# BodyTubeRev.net
KiCad netlist of a schematic drawn in Altium Designer
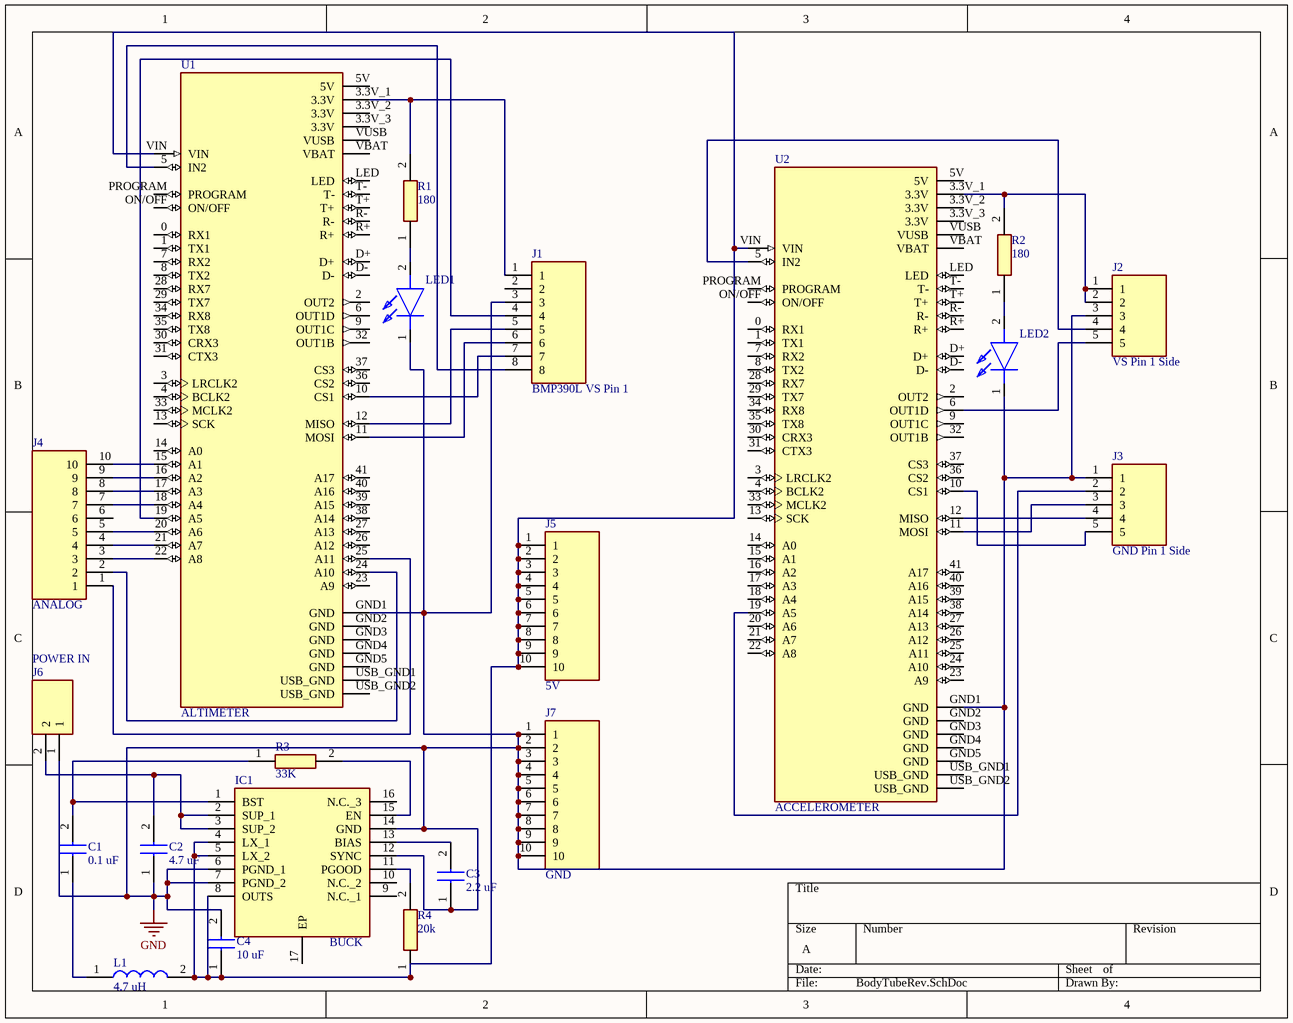
[diagram p0: BodyTubeRev.SchDoc]

(export (version "E")
  (design (tool "Eeschema 10.0.6"))
  (components
    (comp (ref "C1")
      (value "0.1 uF")
      (footprint "SamacSys:CAPC2012X88N")
      (description "Capacitor")
      (fields
        (field (name "MANUFACTURER_PART_NUMBER") "C0805C222K5RAC7025")
        (field (name "MOUSER PART NUMBER") "80-C0805C222K5RACTM")
      )
      (libsource (lib "*") (part "C0805C222K5RAC7025"))
    )
    (comp (ref "C2")
      (value "4.7 uF")
      (footprint "SamacSys:CAPC2012X140N")
      (description "Capacitor")
      (fields
        (field (name "MANUFACTURER_PART_NUMBER") "GRM21BR61H475KE51L")
        (field (name "MOUSER PART NUMBER") "81-GRM21BR61H475KE1L")
      )
      (libsource (lib "SamacSys") (part "GRM21BR61H475KE51L"))
    )
    (comp (ref "C3")
      (value "2.2 uF")
      (footprint "SamacSys:CAPC2012X140N")
      (description "Capacitor")
      (fields (field (name "MANUFACTURER_PART_NUMBER") "C0805C106K8PAC7800"))
      (libsource (lib "SamacSys") (part "C0805C106K8PAC7800"))
    )
    (comp (ref "C4")
      (value "10 uF")
      (footprint "SamacSys:CAPC2012X140N")
      (description "Capacitor")
      (fields (field (name "MANUFACTURER_PART_NUMBER") "C0805C106K8PAC7800"))
      (libsource (lib "SamacSys") (part "C0805C106K8PAC7800"))
    )
    (comp (ref "IC1")
      (value "BUCK")
      (footprint "SamacSys:SOP65P638X110-17N")
      (description "Integrated Circuit")
      (fields
        (field (name "MANUFACTURER_PART_NUMBER") "MAX16903RAUE50/V+")
        (field (name "MOUSER PART NUMBER") "700-16903RAUE50/V+")
      )
      (libsource (lib "SamacSys") (part "MAX16903RAUE50_V+"))
    )
    (comp (ref "J1")
      (value "BMP390L VS Pin 1")
      (footprint "SamacSys:HDRV8W64P0X254_1X8_2032X254X813P")
      (description "Connector")
      (fields
        (field (name "MANUFACTURER_PART_NUMBER") "DW-08-07-T-S-200")
        (field (name "MOUSER PART NUMBER") "200-DW0807TS200")
      )
      (libsource (lib "*") (part "DW-08-07-T-S-200"))
    )
    (comp (ref "J2")
      (value "VS Pin 1 Side")
      (footprint "SamacSys:HDRV5W64P0X254_1X5_1270X254X813P")
      (description "Connector")
      (fields
        (field (name "MANUFACTURER_PART_NUMBER") "DW-05-07-T-S-200")
        (field (name "MOUSER PART NUMBER") "200-DW0507TS200")
      )
      (libsource (lib "*") (part "DW-05-07-T-S-200"))
    )
    (comp (ref "J3")
      (value "GND Pin 1 Side")
      (footprint "SamacSys:HDRV5W64P0X254_1X5_1270X254X813P")
      (description "Connector")
      (fields
        (field (name "MANUFACTURER_PART_NUMBER") "DW-05-07-T-S-200")
        (field (name "MOUSER PART NUMBER") "200-DW0507TS200")
      )
      (libsource (lib "*") (part "DW-05-07-T-S-200"))
    )
    (comp (ref "J4")
      (value "ANALOG")
      (footprint "SamacSys:RHDR10W80P0X254_1X10_2590X254X850P")
      (description "Connector")
      (fields (field (name "MANUFACTURER_PART_NUMBER") "PPTC101LFBN-RC"))
      (libsource (lib "") (part "PPTC101LFBN-RC_1"))
    )
    (comp (ref "J5")
      (value "5V")
      (footprint "SamacSys:RHDR10W80P0X254_1X10_2590X254X850P")
      (description "Connector")
      (fields (field (name "MANUFACTURER_PART_NUMBER") "PPTC101LFBN-RC"))
      (libsource (lib "*") (part "PPTC101LFBN-RC"))
    )
    (comp (ref "J6")
      (value "POWER IN")
      (footprint "SamacSys:0436500201")
      (description "Connector")
      (fields (field (name "MANUFACTURER_PART_NUMBER") "0436500201"))
      (libsource (lib "SamacSys") (part "0436500201"))
    )
    (comp (ref "J7")
      (value "GND")
      (footprint "SamacSys:RHDR10W80P0X254_1X10_2590X254X850P")
      (description "Connector")
      (fields (field (name "MANUFACTURER_PART_NUMBER") "PPTC101LFBN-RC"))
      (libsource (lib "*") (part "PPTC101LFBN-RC"))
    )
    (comp (ref "L1")
      (value "4.7 uH")
      (footprint "SamacSys:LQM2HPN1R0MG0L")
      (description "Inductor")
      (fields
        (field (name "MANUFACTURER_PART_NUMBER") "LQH2HPN4R7MGRL")
        (field (name "MOUSER PART NUMBER") "81-LQH2HPN4R7MGRL")
      )
      (libsource (lib "SamacSys") (part "LQH2HPN4R7MGRL"))
    )
    (comp (ref "LED1")
      (value "~")
      (footprint "SamacSys:LEDC2012X80N")
      (description "LED")
      (fields
        (field (name "MANUFACTURER_PART_NUMBER") "HSMG-C170")
        (field (name "MOUSER PART NUMBER") "630-HSMG-C170")
      )
      (libsource (lib "SamacSys") (part "HSMG-C170"))
    )
    (comp (ref "LED2")
      (value "~")
      (footprint "SamacSys:LEDC2012X80N")
      (description "LED")
      (fields
        (field (name "MANUFACTURER_PART_NUMBER") "HSMG-C170")
        (field (name "MOUSER PART NUMBER") "630-HSMG-C170")
      )
      (libsource (lib "SamacSys") (part "HSMG-C170"))
    )
    (comp (ref "R1")
      (value "180")
      (footprint "SamacSys:ERJ6EN_(0805)")
      (description "Resistor")
      (fields
        (field (name "MANUFACTURER_PART_NUMBER") "ERJ-6ENF1800V")
        (field (name "MOUSER PART NUMBER") "667-ERJ-6ENF1800V")
      )
      (libsource (lib "SamacSys") (part "ERJ-6ENF1800V"))
    )
    (comp (ref "R2")
      (value "180")
      (footprint "SamacSys:ERJ6EN_(0805)")
      (description "Resistor")
      (fields
        (field (name "MANUFACTURER_PART_NUMBER") "ERJ-6ENF1800V")
        (field (name "MOUSER PART NUMBER") "667-ERJ-6ENF1800V")
      )
      (libsource (lib "SamacSys") (part "ERJ-6ENF1800V"))
    )
    (comp (ref "R3")
      (value "33K")
      (footprint "SamacSys:ERJ6ENF1000V")
      (description "Resistor")
      (fields
        (field (name "MANUFACTURER_PART_NUMBER") "ERJ-6ENF33R0V")
        (field (name "MOUSER PART NUMBER") "667-ERJ-6ENF33R0V")
      )
      (libsource (lib "*") (part "ERJ-6ENF33R0V"))
    )
    (comp (ref "R4")
      (value "20k")
      (footprint "SamacSys:RESC2012X70N")
      (description "Resistor")
      (fields
        (field (name "MANUFACTURER_PART_NUMBER") "ERJ-6GEYJ203V")
        (field (name "MOUSER PART NUMBER") "667-ERJ-6GEYJ203V")
      )
      (libsource (lib "SamacSys") (part "ERJ-6GEYJ203V"))
    )
    (comp (ref "U1")
      (value "ALTIMETER")
      (footprint "MODULE_DEV-16771")
      (description "RT1062 Teensy 4.1 i.MX ARM Cortex-M7 MPU Embedded Evaluation Board")
      (fields (field (name "MP") "DEV-16771"))
      (libsource (lib "DEV-16771") (part "DEV-16771"))
    )
    (comp (ref "U2")
      (value "ACCELEROMETER")
      (footprint "MODULE_DEV-16771")
      (description "RT1062 Teensy 4.1 i.MX ARM Cortex-M7 MPU Embedded Evaluation Board")
      (fields (field (name "MP") "DEV-16771"))
      (libsource (lib "DEV-16771") (part "DEV-16771"))
    )
  )
  (nets
    (net (code "1") (name "GND") (class "Default")
      (node (ref "C2") (pin "1") (pinfunction "1_1") (pintype "passive"))
      (node (ref "C3") (pin "1") (pinfunction "1_1") (pintype "passive"))
      (node (ref "C4") (pin "2") (pinfunction "2_2") (pintype "passive"))
      (node (ref "IC1") (pin "12") (pinfunction "SYNC_12") (pintype "passive"))
      (node (ref "IC1") (pin "14") (pinfunction "GND_14") (pintype "passive"))
      (node (ref "IC1") (pin "6") (pinfunction "PGND_1_6") (pintype "passive"))
      (node (ref "IC1") (pin "7") (pinfunction "PGND_2_7") (pintype "passive"))
      (node (ref "J1") (pin "3") (pinfunction "3_3") (pintype "passive"))
      (node (ref "J2") (pin "3") (pinfunction "3_3") (pintype "passive"))
      (node (ref "J3") (pin "1") (pinfunction "1_1") (pintype "passive"))
      (node (ref "J6") (pin "1") (pinfunction "1_1") (pintype "passive"))
      (node (ref "J7") (pin "1") (pinfunction "1_1") (pintype "passive"))
      (node (ref "J7") (pin "10") (pinfunction "10_10") (pintype "passive"))
      (node (ref "J7") (pin "2") (pinfunction "2_2") (pintype "passive"))
      (node (ref "J7") (pin "3") (pinfunction "3_3") (pintype "passive"))
      (node (ref "J7") (pin "4") (pinfunction "4_4") (pintype "passive"))
      (node (ref "J7") (pin "5") (pinfunction "5_5") (pintype "passive"))
      (node (ref "J7") (pin "6") (pinfunction "6_6") (pintype "passive"))
      (node (ref "J7") (pin "7") (pinfunction "7_7") (pintype "passive"))
      (node (ref "J7") (pin "8") (pinfunction "8_8") (pintype "passive"))
      (node (ref "J7") (pin "9") (pinfunction "9_9") (pintype "passive"))
      (node (ref "LED1") (pin "1") (pinfunction "K_1") (pintype "passive"))
      (node (ref "LED2") (pin "1") (pinfunction "K_1") (pintype "passive"))
      (node (ref "U1") (pin "GND1") (pinfunction "GND_GND1") (pintype "power_in"))
      (node (ref "U2") (pin "GND1") (pinfunction "GND_GND1") (pintype "power_in"))
    )
    (net (code "2") (name "Net-(C1-Pad1)") (class "Default")
      (node (ref "C1") (pin "1") (pinfunction "1_1") (pintype "passive"))
      (node (ref "L1") (pin "1") (pinfunction "1_1") (pintype "passive"))
    )
    (net (code "3") (name "Net-(IC1-BIAS)") (class "Default")
      (node (ref "C3") (pin "2") (pinfunction "2_2") (pintype "passive"))
      (node (ref "IC1") (pin "13") (pinfunction "BIAS_13") (pintype "passive"))
    )
    (net (code "4") (name "Net-(IC1-BST)") (class "Default")
      (node (ref "C1") (pin "2") (pinfunction "2_2") (pintype "passive"))
      (node (ref "IC1") (pin "1") (pinfunction "BST_1") (pintype "passive"))
      (node (ref "R3") (pin "1") (pinfunction "1_1") (pintype "passive"))
    )
    (net (code "5") (name "Net-(IC1-EN)") (class "Default")
      (node (ref "IC1") (pin "15") (pinfunction "EN_15") (pintype "passive"))
      (node (ref "R3") (pin "2") (pinfunction "2_2") (pintype "passive"))
    )
    (net (code "6") (name "Net-(IC1-LX_1)") (class "Default")
      (node (ref "C4") (pin "1") (pinfunction "1_1") (pintype "passive"))
      (node (ref "IC1") (pin "4") (pinfunction "LX_1_4") (pintype "passive"))
      (node (ref "IC1") (pin "5") (pinfunction "LX_2_5") (pintype "passive"))
      (node (ref "IC1") (pin "8") (pinfunction "OUTS_8") (pintype "passive"))
      (node (ref "J5") (pin "1") (pinfunction "1_1") (pintype "passive"))
      (node (ref "J5") (pin "10") (pinfunction "10_10") (pintype "passive"))
      (node (ref "J5") (pin "2") (pinfunction "2_2") (pintype "passive"))
      (node (ref "J5") (pin "3") (pinfunction "3_3") (pintype "passive"))
      (node (ref "J5") (pin "4") (pinfunction "4_4") (pintype "passive"))
      (node (ref "J5") (pin "5") (pinfunction "5_5") (pintype "passive"))
      (node (ref "J5") (pin "6") (pinfunction "6_6") (pintype "passive"))
      (node (ref "J5") (pin "7") (pinfunction "7_7") (pintype "passive"))
      (node (ref "J5") (pin "8") (pinfunction "8_8") (pintype "passive"))
      (node (ref "J5") (pin "9") (pinfunction "9_9") (pintype "passive"))
      (node (ref "L1") (pin "2") (pinfunction "2_2") (pintype "passive"))
      (node (ref "R4") (pin "1") (pinfunction "1_1") (pintype "passive"))
      (node (ref "U1") (pin "VIN") (pinfunction "VIN_VIN") (pintype "input"))
      (node (ref "U2") (pin "VIN") (pinfunction "VIN_VIN") (pintype "input"))
    )
    (net (code "7") (name "Net-(IC1-PGOOD)") (class "Default")
      (node (ref "IC1") (pin "11") (pinfunction "PGOOD_11") (pintype "passive"))
      (node (ref "R4") (pin "2") (pinfunction "2_2") (pintype "passive"))
    )
    (net (code "8") (name "Net-(IC1-SUP_1)") (class "Default")
      (node (ref "C2") (pin "2") (pinfunction "2_2") (pintype "passive"))
      (node (ref "IC1") (pin "2") (pinfunction "SUP_1_2") (pintype "passive"))
      (node (ref "IC1") (pin "3") (pinfunction "SUP_2_3") (pintype "passive"))
      (node (ref "J6") (pin "2") (pinfunction "2_2") (pintype "passive"))
    )
    (net (code "9") (name "Net-(J1-Pad1)") (class "Default")
      (node (ref "J1") (pin "1") (pinfunction "1_1") (pintype "passive"))
      (node (ref "R1") (pin "2") (pinfunction "2_2") (pintype "passive"))
      (node (ref "U1") (pin "3.3V_1") (pinfunction "3.3V_3.3V_1") (pintype "power_in"))
    )
    (net (code "10") (name "Net-(J2-Pad1)") (class "Default")
      (node (ref "J2") (pin "1") (pinfunction "1_1") (pintype "passive"))
      (node (ref "J2") (pin "2") (pinfunction "2_2") (pintype "passive"))
      (node (ref "R2") (pin "2") (pinfunction "2_2") (pintype "passive"))
      (node (ref "U2") (pin "3.3V_1") (pinfunction "3.3V_3.3V_1") (pintype "power_in"))
    )
    (net (code "11") (name "Net-(LED1-A)") (class "Default")
      (node (ref "LED1") (pin "2") (pinfunction "A_2") (pintype "passive"))
      (node (ref "R1") (pin "1") (pinfunction "1_1") (pintype "passive"))
    )
    (net (code "12") (name "Net-(LED2-A)") (class "Default")
      (node (ref "LED2") (pin "2") (pinfunction "A_2") (pintype "passive"))
      (node (ref "R2") (pin "1") (pinfunction "1_1") (pintype "passive"))
    )
    (net (code "13") (name "Net-(U1-A1)") (class "Default")
      (node (ref "J4") (pin "10") (pinfunction "10_10") (pintype "passive"))
      (node (ref "U1") (pin "15") (pinfunction "A1_15") (pintype "bidirectional"))
    )
    (net (code "14") (name "Net-(U1-A2)") (class "Default")
      (node (ref "J4") (pin "9") (pinfunction "9_9") (pintype "passive"))
      (node (ref "U1") (pin "16") (pinfunction "A2_16") (pintype "bidirectional"))
    )
    (net (code "15") (name "Net-(U1-A3)") (class "Default")
      (node (ref "J4") (pin "8") (pinfunction "8_8") (pintype "passive"))
      (node (ref "U1") (pin "17") (pinfunction "A3_17") (pintype "bidirectional"))
    )
    (net (code "16") (name "Net-(U1-A4)") (class "Default")
      (node (ref "J4") (pin "7") (pinfunction "7_7") (pintype "passive"))
      (node (ref "U1") (pin "18") (pinfunction "A4_18") (pintype "bidirectional"))
    )
    (net (code "17") (name "Net-(U1-A5)") (class "Default")
      (node (ref "J1") (pin "4") (pinfunction "4_4") (pintype "passive"))
      (node (ref "U1") (pin "19") (pinfunction "A5_19") (pintype "bidirectional"))
    )
    (net (code "18") (name "Net-(U1-A6)") (class "Default")
      (node (ref "J4") (pin "5") (pinfunction "5_5") (pintype "passive"))
      (node (ref "U1") (pin "20") (pinfunction "A6_20") (pintype "bidirectional"))
    )
    (net (code "19") (name "Net-(U1-A7)") (class "Default")
      (node (ref "J4") (pin "4") (pinfunction "4_4") (pintype "passive"))
      (node (ref "U1") (pin "21") (pinfunction "A7_21") (pintype "bidirectional"))
    )
    (net (code "20") (name "Net-(U1-A8)") (class "Default")
      (node (ref "J4") (pin "3") (pinfunction "3_3") (pintype "passive"))
      (node (ref "U1") (pin "22") (pinfunction "A8_22") (pintype "bidirectional"))
    )
    (net (code "21") (name "Net-(U1-A10)") (class "Default")
      (node (ref "J4") (pin "2") (pinfunction "2_2") (pintype "passive"))
      (node (ref "U1") (pin "24") (pinfunction "A10_24") (pintype "bidirectional"))
    )
    (net (code "22") (name "Net-(U1-A11)") (class "Default")
      (node (ref "J4") (pin "1") (pinfunction "1_1") (pintype "passive"))
      (node (ref "U1") (pin "25") (pinfunction "A11_25") (pintype "bidirectional"))
    )
    (net (code "23") (name "Net-(U1-CS1)") (class "Default")
      (node (ref "J1") (pin "7") (pinfunction "7_7") (pintype "passive"))
      (node (ref "U1") (pin "10") (pinfunction "CS1_10") (pintype "bidirectional"))
    )
    (net (code "24") (name "Net-(U1-IN2)") (class "Default")
      (node (ref "J1") (pin "8") (pinfunction "8_8") (pintype "passive"))
      (node (ref "U1") (pin "5") (pinfunction "IN2_5") (pintype "bidirectional"))
    )
    (net (code "25") (name "Net-(U1-MISO)") (class "Default")
      (node (ref "J1") (pin "5") (pinfunction "5_5") (pintype "passive"))
      (node (ref "U1") (pin "12") (pinfunction "MISO_12") (pintype "bidirectional"))
    )
    (net (code "26") (name "Net-(U1-MOSI)") (class "Default")
      (node (ref "J1") (pin "6") (pinfunction "6_6") (pintype "passive"))
      (node (ref "U1") (pin "11") (pinfunction "MOSI_11") (pintype "bidirectional"))
    )
    (net (code "27") (name "Net-(U2-A5)") (class "Default")
      (node (ref "J3") (pin "2") (pinfunction "2_2") (pintype "passive"))
      (node (ref "U2") (pin "19") (pinfunction "A5_19") (pintype "bidirectional"))
    )
    (net (code "28") (name "Net-(U2-CS1)") (class "Default")
      (node (ref "J3") (pin "5") (pinfunction "5_5") (pintype "passive"))
      (node (ref "U2") (pin "10") (pinfunction "CS1_10") (pintype "bidirectional"))
    )
    (net (code "29") (name "Net-(U2-IN2)") (class "Default")
      (node (ref "J2") (pin "4") (pinfunction "4_4") (pintype "passive"))
      (node (ref "U2") (pin "5") (pinfunction "IN2_5") (pintype "bidirectional"))
    )
    (net (code "30") (name "Net-(U2-MISO)") (class "Default")
      (node (ref "J3") (pin "4") (pinfunction "4_4") (pintype "passive"))
      (node (ref "U2") (pin "12") (pinfunction "MISO_12") (pintype "bidirectional"))
    )
    (net (code "31") (name "Net-(U2-MOSI)") (class "Default")
      (node (ref "J3") (pin "3") (pinfunction "3_3") (pintype "passive"))
      (node (ref "U2") (pin "11") (pinfunction "MOSI_11") (pintype "bidirectional"))
    )
    (net (code "32") (name "Net-(U2-OUT1D)") (class "Default")
      (node (ref "J2") (pin "5") (pinfunction "5_5") (pintype "passive"))
      (node (ref "U2") (pin "6") (pinfunction "OUT1D_6") (pintype "output"))
    )
    (net (code "33") (name "unconnected-(IC1-EP-Pad17)") (class "Default")
      (node (ref "IC1") (pin "17") (pinfunction "EP_17") (pintype "passive"))
    )
    (net (code "34") (name "unconnected-(IC1-N.C._1-Pad9)") (class "Default")
      (node (ref "IC1") (pin "9") (pinfunction "N.C._1_9") (pintype "passive"))
    )
    (net (code "35") (name "unconnected-(IC1-N.C._2-Pad10)") (class "Default")
      (node (ref "IC1") (pin "10") (pinfunction "N.C._2_10") (pintype "passive"))
    )
    (net (code "36") (name "unconnected-(IC1-N.C._3-Pad16)") (class "Default")
      (node (ref "IC1") (pin "16") (pinfunction "N.C._3_16") (pintype "passive"))
    )
    (net (code "37") (name "unconnected-(J1-Pad2)") (class "Default")
      (node (ref "J1") (pin "2") (pinfunction "2_2") (pintype "passive"))
    )
    (net (code "38") (name "unconnected-(J4-Pad6)") (class "Default")
      (node (ref "J4") (pin "6") (pinfunction "6_6") (pintype "passive"))
    )
    (net (code "39") (name "unconnected-(U1-3.3V-Pad3.3V_2)") (class "Default")
      (node (ref "U1") (pin "3.3V_2") (pinfunction "3.3V_3.3V_2") (pintype "power_in"))
    )
    (net (code "40") (name "unconnected-(U1-3.3V-Pad3.3V_3)") (class "Default")
      (node (ref "U1") (pin "3.3V_3") (pinfunction "3.3V_3.3V_3") (pintype "power_in"))
    )
    (net (code "41") (name "unconnected-(U1-A0-Pad14)") (class "Default")
      (node (ref "U1") (pin "14") (pinfunction "A0_14") (pintype "bidirectional"))
    )
    (net (code "42") (name "unconnected-(U1-A9-Pad23)") (class "Default")
      (node (ref "U1") (pin "23") (pinfunction "A9_23") (pintype "bidirectional"))
    )
    (net (code "43") (name "unconnected-(U1-A12-Pad26)") (class "Default")
      (node (ref "U1") (pin "26") (pinfunction "A12_26") (pintype "bidirectional"))
    )
    (net (code "44") (name "unconnected-(U1-A13-Pad27)") (class "Default")
      (node (ref "U1") (pin "27") (pinfunction "A13_27") (pintype "bidirectional"))
    )
    (net (code "45") (name "unconnected-(U1-A14-Pad38)") (class "Default")
      (node (ref "U1") (pin "38") (pinfunction "A14_38") (pintype "bidirectional"))
    )
    (net (code "46") (name "unconnected-(U1-A15-Pad39)") (class "Default")
      (node (ref "U1") (pin "39") (pinfunction "A15_39") (pintype "bidirectional"))
    )
    (net (code "47") (name "unconnected-(U1-A16-Pad40)") (class "Default")
      (node (ref "U1") (pin "40") (pinfunction "A16_40") (pintype "bidirectional"))
    )
    (net (code "48") (name "unconnected-(U1-A17-Pad41)") (class "Default")
      (node (ref "U1") (pin "41") (pinfunction "A17_41") (pintype "bidirectional"))
    )
    (net (code "49") (name "unconnected-(U1-BCLK2-Pad4)") (class "Default")
      (node (ref "U1") (pin "4") (pinfunction "BCLK2_4") (pintype "bidirectional"))
    )
    (net (code "50") (name "unconnected-(U1-CRX3-Pad30)") (class "Default")
      (node (ref "U1") (pin "30") (pinfunction "CRX3_30") (pintype "bidirectional"))
    )
    (net (code "51") (name "unconnected-(U1-CS2-Pad36)") (class "Default")
      (node (ref "U1") (pin "36") (pinfunction "CS2_36") (pintype "bidirectional"))
    )
    (net (code "52") (name "unconnected-(U1-CS3-Pad37)") (class "Default")
      (node (ref "U1") (pin "37") (pinfunction "CS3_37") (pintype "bidirectional"))
    )
    (net (code "53") (name "unconnected-(U1-CTX3-Pad31)") (class "Default")
      (node (ref "U1") (pin "31") (pinfunction "CTX3_31") (pintype "bidirectional"))
    )
    (net (code "54") (name "unconnected-(U1-GND-PadGND2)") (class "Default")
      (node (ref "U1") (pin "GND2") (pinfunction "GND_GND2") (pintype "power_in"))
    )
    (net (code "55") (name "unconnected-(U1-GND-PadGND3)") (class "Default")
      (node (ref "U1") (pin "GND3") (pinfunction "GND_GND3") (pintype "power_in"))
    )
    (net (code "56") (name "unconnected-(U1-GND-PadGND4)") (class "Default")
      (node (ref "U1") (pin "GND4") (pinfunction "GND_GND4") (pintype "power_in"))
    )
    (net (code "57") (name "unconnected-(U1-GND-PadGND5)") (class "Default")
      (node (ref "U1") (pin "GND5") (pinfunction "GND_GND5") (pintype "power_in"))
    )
    (net (code "58") (name "unconnected-(U1-LRCLK2-Pad3)") (class "Default")
      (node (ref "U1") (pin "3") (pinfunction "LRCLK2_3") (pintype "bidirectional"))
    )
    (net (code "59") (name "unconnected-(U1-MCLK2-Pad33)") (class "Default")
      (node (ref "U1") (pin "33") (pinfunction "MCLK2_33") (pintype "bidirectional"))
    )
    (net (code "60") (name "unconnected-(U1-OUT1B-Pad32)") (class "Default")
      (node (ref "U1") (pin "32") (pinfunction "OUT1B_32") (pintype "output"))
    )
    (net (code "61") (name "unconnected-(U1-OUT1C-Pad9)") (class "Default")
      (node (ref "U1") (pin "9") (pinfunction "OUT1C_9") (pintype "output"))
    )
    (net (code "62") (name "unconnected-(U1-OUT1D-Pad6)") (class "Default")
      (node (ref "U1") (pin "6") (pinfunction "OUT1D_6") (pintype "output"))
    )
    (net (code "63") (name "unconnected-(U1-OUT2-Pad2)") (class "Default")
      (node (ref "U1") (pin "2") (pinfunction "OUT2_2") (pintype "output"))
    )
    (net (code "64") (name "unconnected-(U1-Pad5V)") (class "Default")
      (node (ref "U1") (pin "5V") (pinfunction "5V_5V") (pintype "power_in"))
    )
    (net (code "65") (name "unconnected-(U1-PadD+)") (class "Default")
      (node (ref "U1") (pin "D+") (pinfunction "D+_D+") (pintype "bidirectional"))
    )
    (net (code "66") (name "unconnected-(U1-PadD-)") (class "Default")
      (node (ref "U1") (pin "D-") (pinfunction "D-_D-") (pintype "bidirectional"))
    )
    (net (code "67") (name "unconnected-(U1-PadLED)") (class "Default")
      (node (ref "U1") (pin "LED") (pinfunction "LED_LED") (pintype "bidirectional"))
    )
    (net (code "68") (name "unconnected-(U1-PadON{slash}OFF)") (class "Default")
      (node (ref "U1") (pin "ON/OFF") (pinfunction "ON/OFF_ON/OFF") (pintype "bidirectional"))
    )
    (net (code "69") (name "unconnected-(U1-PadPROGRAM)") (class "Default")
      (node (ref "U1") (pin "PROGRAM") (pinfunction "PROGRAM_PROGRAM") (pintype "bidirectional"))
    )
    (net (code "70") (name "unconnected-(U1-PadR+)") (class "Default")
      (node (ref "U1") (pin "R+") (pinfunction "R+_R+") (pintype "bidirectional"))
    )
    (net (code "71") (name "unconnected-(U1-PadR-)") (class "Default")
      (node (ref "U1") (pin "R-") (pinfunction "R-_R-") (pintype "bidirectional"))
    )
    (net (code "72") (name "unconnected-(U1-PadT+)") (class "Default")
      (node (ref "U1") (pin "T+") (pinfunction "T+_T+") (pintype "bidirectional"))
    )
    (net (code "73") (name "unconnected-(U1-PadT-)") (class "Default")
      (node (ref "U1") (pin "T-") (pinfunction "T-_T-") (pintype "bidirectional"))
    )
    (net (code "74") (name "unconnected-(U1-PadVBAT)") (class "Default")
      (node (ref "U1") (pin "VBAT") (pinfunction "VBAT_VBAT") (pintype "passive"))
    )
    (net (code "75") (name "unconnected-(U1-PadVUSB)") (class "Default")
      (node (ref "U1") (pin "VUSB") (pinfunction "VUSB_VUSB") (pintype "passive"))
    )
    (net (code "76") (name "unconnected-(U1-RX1-Pad0)") (class "Default")
      (node (ref "U1") (pin "0") (pinfunction "RX1_0") (pintype "bidirectional"))
    )
    (net (code "77") (name "unconnected-(U1-RX2-Pad7)") (class "Default")
      (node (ref "U1") (pin "7") (pinfunction "RX2_7") (pintype "bidirectional"))
    )
    (net (code "78") (name "unconnected-(U1-RX7-Pad28)") (class "Default")
      (node (ref "U1") (pin "28") (pinfunction "RX7_28") (pintype "bidirectional"))
    )
    (net (code "79") (name "unconnected-(U1-RX8-Pad34)") (class "Default")
      (node (ref "U1") (pin "34") (pinfunction "RX8_34") (pintype "bidirectional"))
    )
    (net (code "80") (name "unconnected-(U1-SCK-Pad13)") (class "Default")
      (node (ref "U1") (pin "13") (pinfunction "SCK_13") (pintype "bidirectional"))
    )
    (net (code "81") (name "unconnected-(U1-TX1-Pad1)") (class "Default")
      (node (ref "U1") (pin "1") (pinfunction "TX1_1") (pintype "bidirectional"))
    )
    (net (code "82") (name "unconnected-(U1-TX2-Pad8)") (class "Default")
      (node (ref "U1") (pin "8") (pinfunction "TX2_8") (pintype "bidirectional"))
    )
    (net (code "83") (name "unconnected-(U1-TX7-Pad29)") (class "Default")
      (node (ref "U1") (pin "29") (pinfunction "TX7_29") (pintype "bidirectional"))
    )
    (net (code "84") (name "unconnected-(U1-TX8-Pad35)") (class "Default")
      (node (ref "U1") (pin "35") (pinfunction "TX8_35") (pintype "bidirectional"))
    )
    (net (code "85") (name "unconnected-(U1-USB_GND-PadUSB_GND1)") (class "Default")
      (node (ref "U1") (pin "USB_GND1") (pinfunction "USB_GND_USB_GND1") (pintype "power_in"))
    )
    (net (code "86") (name "unconnected-(U1-USB_GND-PadUSB_GND2)") (class "Default")
      (node (ref "U1") (pin "USB_GND2") (pinfunction "USB_GND_USB_GND2") (pintype "power_in"))
    )
    (net (code "87") (name "unconnected-(U2-3.3V-Pad3.3V_2)") (class "Default")
      (node (ref "U2") (pin "3.3V_2") (pinfunction "3.3V_3.3V_2") (pintype "power_in"))
    )
    (net (code "88") (name "unconnected-(U2-3.3V-Pad3.3V_3)") (class "Default")
      (node (ref "U2") (pin "3.3V_3") (pinfunction "3.3V_3.3V_3") (pintype "power_in"))
    )
    (net (code "89") (name "unconnected-(U2-A0-Pad14)") (class "Default")
      (node (ref "U2") (pin "14") (pinfunction "A0_14") (pintype "bidirectional"))
    )
    (net (code "90") (name "unconnected-(U2-A1-Pad15)") (class "Default")
      (node (ref "U2") (pin "15") (pinfunction "A1_15") (pintype "bidirectional"))
    )
    (net (code "91") (name "unconnected-(U2-A2-Pad16)") (class "Default")
      (node (ref "U2") (pin "16") (pinfunction "A2_16") (pintype "bidirectional"))
    )
    (net (code "92") (name "unconnected-(U2-A3-Pad17)") (class "Default")
      (node (ref "U2") (pin "17") (pinfunction "A3_17") (pintype "bidirectional"))
    )
    (net (code "93") (name "unconnected-(U2-A4-Pad18)") (class "Default")
      (node (ref "U2") (pin "18") (pinfunction "A4_18") (pintype "bidirectional"))
    )
    (net (code "94") (name "unconnected-(U2-A6-Pad20)") (class "Default")
      (node (ref "U2") (pin "20") (pinfunction "A6_20") (pintype "bidirectional"))
    )
    (net (code "95") (name "unconnected-(U2-A7-Pad21)") (class "Default")
      (node (ref "U2") (pin "21") (pinfunction "A7_21") (pintype "bidirectional"))
    )
    (net (code "96") (name "unconnected-(U2-A8-Pad22)") (class "Default")
      (node (ref "U2") (pin "22") (pinfunction "A8_22") (pintype "bidirectional"))
    )
    (net (code "97") (name "unconnected-(U2-A9-Pad23)") (class "Default")
      (node (ref "U2") (pin "23") (pinfunction "A9_23") (pintype "bidirectional"))
    )
    (net (code "98") (name "unconnected-(U2-A10-Pad24)") (class "Default")
      (node (ref "U2") (pin "24") (pinfunction "A10_24") (pintype "bidirectional"))
    )
    (net (code "99") (name "unconnected-(U2-A11-Pad25)") (class "Default")
      (node (ref "U2") (pin "25") (pinfunction "A11_25") (pintype "bidirectional"))
    )
    (net (code "100") (name "unconnected-(U2-A12-Pad26)") (class "Default")
      (node (ref "U2") (pin "26") (pinfunction "A12_26") (pintype "bidirectional"))
    )
    (net (code "101") (name "unconnected-(U2-A13-Pad27)") (class "Default")
      (node (ref "U2") (pin "27") (pinfunction "A13_27") (pintype "bidirectional"))
    )
    (net (code "102") (name "unconnected-(U2-A14-Pad38)") (class "Default")
      (node (ref "U2") (pin "38") (pinfunction "A14_38") (pintype "bidirectional"))
    )
    (net (code "103") (name "unconnected-(U2-A15-Pad39)") (class "Default")
      (node (ref "U2") (pin "39") (pinfunction "A15_39") (pintype "bidirectional"))
    )
    (net (code "104") (name "unconnected-(U2-A16-Pad40)") (class "Default")
      (node (ref "U2") (pin "40") (pinfunction "A16_40") (pintype "bidirectional"))
    )
    (net (code "105") (name "unconnected-(U2-A17-Pad41)") (class "Default")
      (node (ref "U2") (pin "41") (pinfunction "A17_41") (pintype "bidirectional"))
    )
    (net (code "106") (name "unconnected-(U2-BCLK2-Pad4)") (class "Default")
      (node (ref "U2") (pin "4") (pinfunction "BCLK2_4") (pintype "bidirectional"))
    )
    (net (code "107") (name "unconnected-(U2-CRX3-Pad30)") (class "Default")
      (node (ref "U2") (pin "30") (pinfunction "CRX3_30") (pintype "bidirectional"))
    )
    (net (code "108") (name "unconnected-(U2-CS2-Pad36)") (class "Default")
      (node (ref "U2") (pin "36") (pinfunction "CS2_36") (pintype "bidirectional"))
    )
    (net (code "109") (name "unconnected-(U2-CS3-Pad37)") (class "Default")
      (node (ref "U2") (pin "37") (pinfunction "CS3_37") (pintype "bidirectional"))
    )
    (net (code "110") (name "unconnected-(U2-CTX3-Pad31)") (class "Default")
      (node (ref "U2") (pin "31") (pinfunction "CTX3_31") (pintype "bidirectional"))
    )
    (net (code "111") (name "unconnected-(U2-GND-PadGND2)") (class "Default")
      (node (ref "U2") (pin "GND2") (pinfunction "GND_GND2") (pintype "power_in"))
    )
    (net (code "112") (name "unconnected-(U2-GND-PadGND3)") (class "Default")
      (node (ref "U2") (pin "GND3") (pinfunction "GND_GND3") (pintype "power_in"))
    )
    (net (code "113") (name "unconnected-(U2-GND-PadGND4)") (class "Default")
      (node (ref "U2") (pin "GND4") (pinfunction "GND_GND4") (pintype "power_in"))
    )
    (net (code "114") (name "unconnected-(U2-GND-PadGND5)") (class "Default")
      (node (ref "U2") (pin "GND5") (pinfunction "GND_GND5") (pintype "power_in"))
    )
    (net (code "115") (name "unconnected-(U2-LRCLK2-Pad3)") (class "Default")
      (node (ref "U2") (pin "3") (pinfunction "LRCLK2_3") (pintype "bidirectional"))
    )
    (net (code "116") (name "unconnected-(U2-MCLK2-Pad33)") (class "Default")
      (node (ref "U2") (pin "33") (pinfunction "MCLK2_33") (pintype "bidirectional"))
    )
    (net (code "117") (name "unconnected-(U2-OUT1B-Pad32)") (class "Default")
      (node (ref "U2") (pin "32") (pinfunction "OUT1B_32") (pintype "output"))
    )
    (net (code "118") (name "unconnected-(U2-OUT1C-Pad9)") (class "Default")
      (node (ref "U2") (pin "9") (pinfunction "OUT1C_9") (pintype "output"))
    )
    (net (code "119") (name "unconnected-(U2-OUT2-Pad2)") (class "Default")
      (node (ref "U2") (pin "2") (pinfunction "OUT2_2") (pintype "output"))
    )
    (net (code "120") (name "unconnected-(U2-Pad5V)") (class "Default")
      (node (ref "U2") (pin "5V") (pinfunction "5V_5V") (pintype "power_in"))
    )
    (net (code "121") (name "unconnected-(U2-PadD+)") (class "Default")
      (node (ref "U2") (pin "D+") (pinfunction "D+_D+") (pintype "bidirectional"))
    )
    (net (code "122") (name "unconnected-(U2-PadD-)") (class "Default")
      (node (ref "U2") (pin "D-") (pinfunction "D-_D-") (pintype "bidirectional"))
    )
    (net (code "123") (name "unconnected-(U2-PadLED)") (class "Default")
      (node (ref "U2") (pin "LED") (pinfunction "LED_LED") (pintype "bidirectional"))
    )
    (net (code "124") (name "unconnected-(U2-PadON{slash}OFF)") (class "Default")
      (node (ref "U2") (pin "ON/OFF") (pinfunction "ON/OFF_ON/OFF") (pintype "bidirectional"))
    )
    (net (code "125") (name "unconnected-(U2-PadPROGRAM)") (class "Default")
      (node (ref "U2") (pin "PROGRAM") (pinfunction "PROGRAM_PROGRAM") (pintype "bidirectional"))
    )
    (net (code "126") (name "unconnected-(U2-PadR+)") (class "Default")
      (node (ref "U2") (pin "R+") (pinfunction "R+_R+") (pintype "bidirectional"))
    )
    (net (code "127") (name "unconnected-(U2-PadR-)") (class "Default")
      (node (ref "U2") (pin "R-") (pinfunction "R-_R-") (pintype "bidirectional"))
    )
    (net (code "128") (name "unconnected-(U2-PadT+)") (class "Default")
      (node (ref "U2") (pin "T+") (pinfunction "T+_T+") (pintype "bidirectional"))
    )
    (net (code "129") (name "unconnected-(U2-PadT-)") (class "Default")
      (node (ref "U2") (pin "T-") (pinfunction "T-_T-") (pintype "bidirectional"))
    )
    (net (code "130") (name "unconnected-(U2-PadVBAT)") (class "Default")
      (node (ref "U2") (pin "VBAT") (pinfunction "VBAT_VBAT") (pintype "passive"))
    )
    (net (code "131") (name "unconnected-(U2-PadVUSB)") (class "Default")
      (node (ref "U2") (pin "VUSB") (pinfunction "VUSB_VUSB") (pintype "passive"))
    )
    (net (code "132") (name "unconnected-(U2-RX1-Pad0)") (class "Default")
      (node (ref "U2") (pin "0") (pinfunction "RX1_0") (pintype "bidirectional"))
    )
    (net (code "133") (name "unconnected-(U2-RX2-Pad7)") (class "Default")
      (node (ref "U2") (pin "7") (pinfunction "RX2_7") (pintype "bidirectional"))
    )
    (net (code "134") (name "unconnected-(U2-RX7-Pad28)") (class "Default")
      (node (ref "U2") (pin "28") (pinfunction "RX7_28") (pintype "bidirectional"))
    )
    (net (code "135") (name "unconnected-(U2-RX8-Pad34)") (class "Default")
      (node (ref "U2") (pin "34") (pinfunction "RX8_34") (pintype "bidirectional"))
    )
    (net (code "136") (name "unconnected-(U2-SCK-Pad13)") (class "Default")
      (node (ref "U2") (pin "13") (pinfunction "SCK_13") (pintype "bidirectional"))
    )
    (net (code "137") (name "unconnected-(U2-TX1-Pad1)") (class "Default")
      (node (ref "U2") (pin "1") (pinfunction "TX1_1") (pintype "bidirectional"))
    )
    (net (code "138") (name "unconnected-(U2-TX2-Pad8)") (class "Default")
      (node (ref "U2") (pin "8") (pinfunction "TX2_8") (pintype "bidirectional"))
    )
    (net (code "139") (name "unconnected-(U2-TX7-Pad29)") (class "Default")
      (node (ref "U2") (pin "29") (pinfunction "TX7_29") (pintype "bidirectional"))
    )
    (net (code "140") (name "unconnected-(U2-TX8-Pad35)") (class "Default")
      (node (ref "U2") (pin "35") (pinfunction "TX8_35") (pintype "bidirectional"))
    )
    (net (code "141") (name "unconnected-(U2-USB_GND-PadUSB_GND1)") (class "Default")
      (node (ref "U2") (pin "USB_GND1") (pinfunction "USB_GND_USB_GND1") (pintype "power_in"))
    )
    (net (code "142") (name "unconnected-(U2-USB_GND-PadUSB_GND2)") (class "Default")
      (node (ref "U2") (pin "USB_GND2") (pinfunction "USB_GND_USB_GND2") (pintype "power_in"))
    )
  )
)
